# barebonesarduino.net
KiCad netlist of a schematic drawn in EAGLE
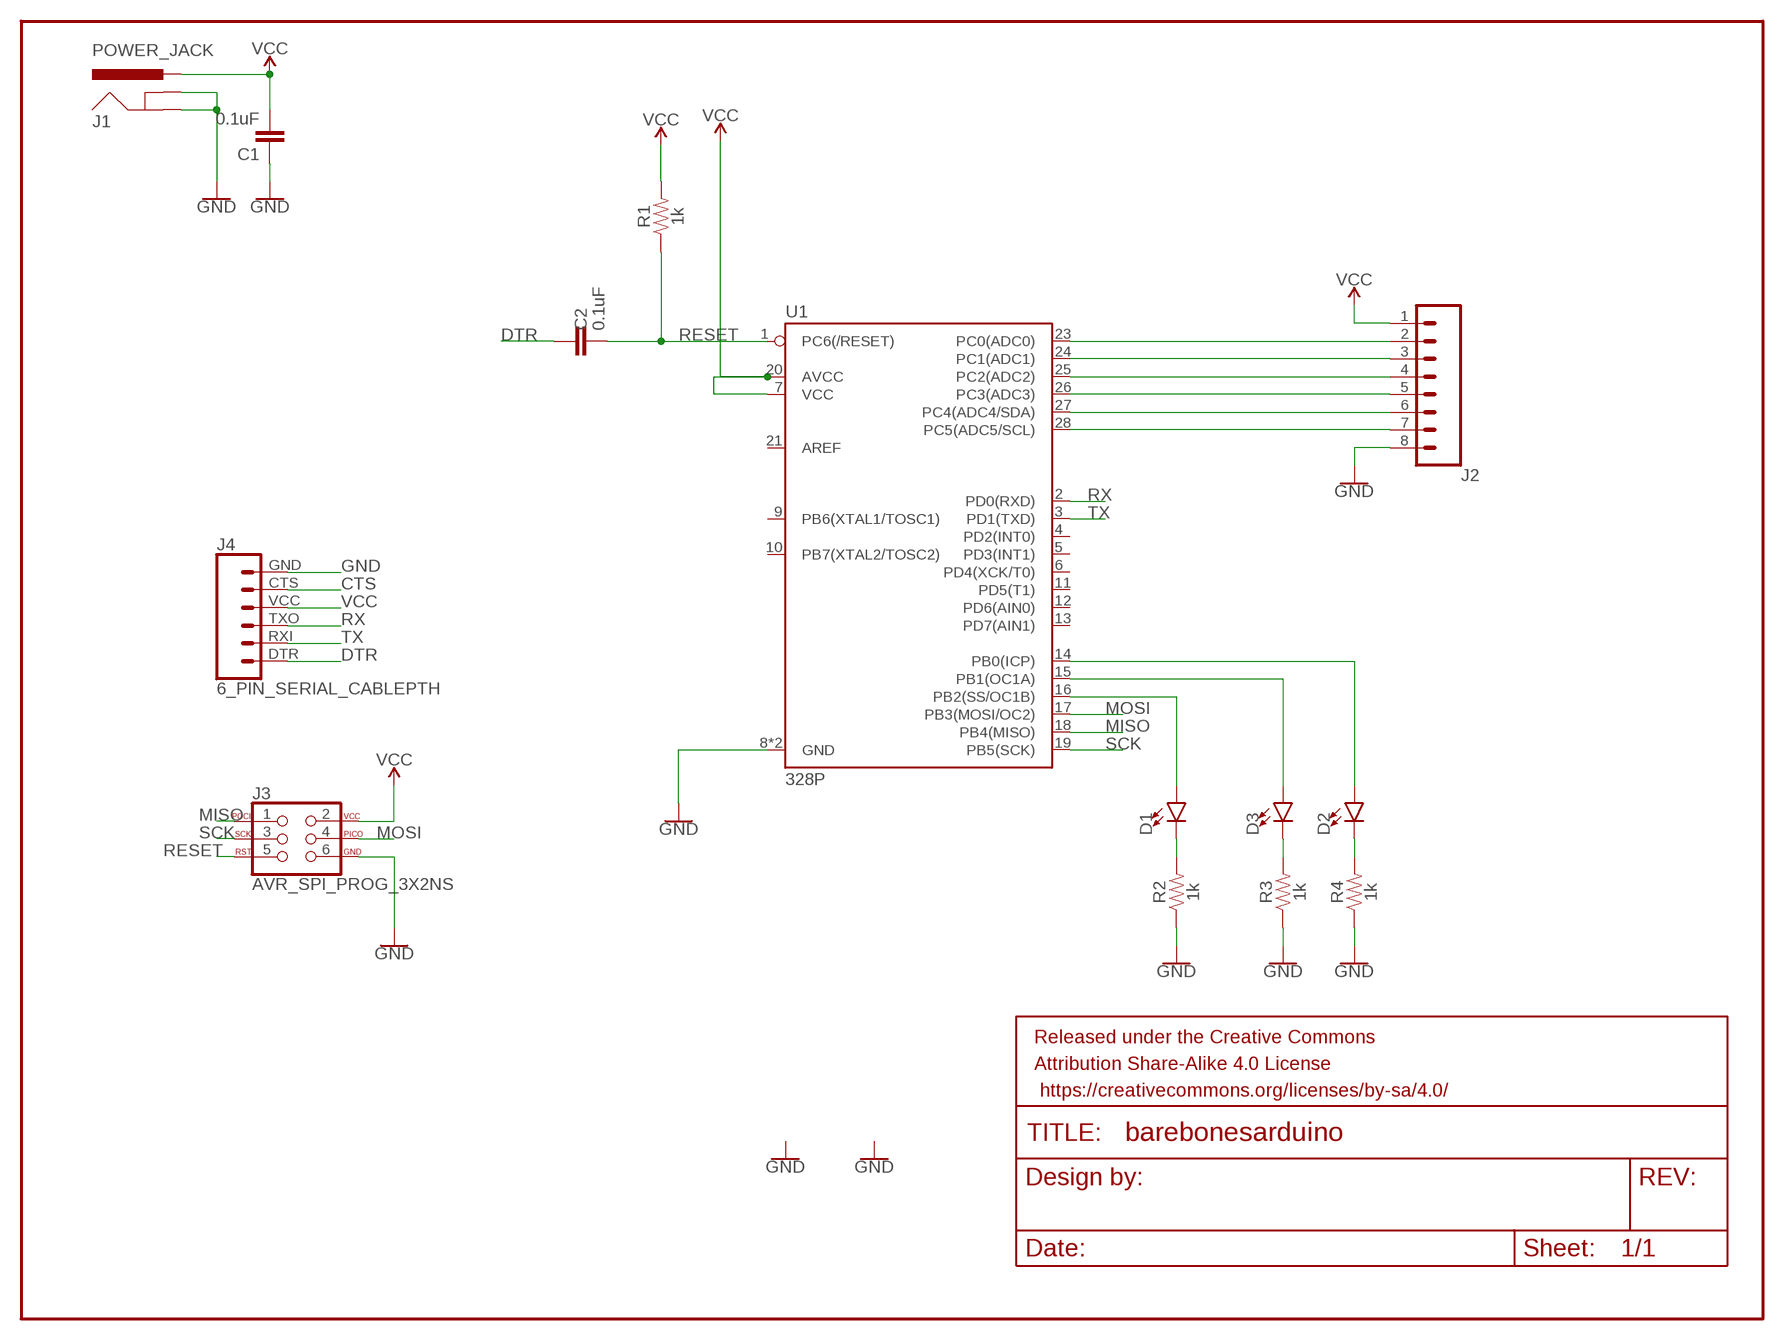
[diagram p0: schematic, sheet 1]

(export (version "E")
  (design (tool "Eeschema 10.0.6"))
  (components
    (comp (ref "C1")
      (value "0.1uF")
      (footprint "eagle-import:CAP-PTH-SMALL-KIT")
      (libsource (lib "eagle-import") (part "0.1UF-KIT-EZ-50V-20%"))
    )
    (comp (ref "C2")
      (value "0.1uF")
      (footprint "eagle-import:CAP-PTH-SMALL-KIT")
      (libsource (lib "eagle-import") (part "0.1UF-KIT-EZ-50V-20%"))
    )
    (comp (ref "D1")
      (value "LED5MM")
      (footprint "eagle-import:LED_5MM")
      (libsource (lib "eagle-import") (part "LED5MM"))
    )
    (comp (ref "D2")
      (value "LED5MM")
      (footprint "eagle-import:LED_5MM")
      (libsource (lib "eagle-import") (part "LED5MM"))
    )
    (comp (ref "D3")
      (value "LED5MM")
      (footprint "eagle-import:LED_5MM")
      (libsource (lib "eagle-import") (part "LED5MM"))
    )
    (comp (ref "FRAME1")
      (value "FRAME-LETTER")
      (footprint "eagle-import:CREATIVE_COMMONS")
      (libsource (lib "eagle-import") (part "FRAME-LETTER"))
    )
    (comp (ref "J1")
      (value "POWER_JACK")
      (footprint "eagle-import:POWER_JACK_PTH")
      (libsource (lib "eagle-import") (part "POWER_JACK"))
    )
    (comp (ref "J2")
      (value "CONN_08\"")
      (footprint "eagle-import:1X08")
      (libsource (lib "eagle-import") (part "CONN_08{dblquote}"))
    )
    (comp (ref "J3")
      (value "AVR_SPI_PROG_3X2NS")
      (footprint "eagle-import:2X3-NS")
      (libsource (lib "eagle-import") (part "AVR_SPI_PROG_3X2NS"))
    )
    (comp (ref "J4")
      (value "6_PIN_SERIAL_CABLEPTH")
      (footprint "eagle-import:FTDI_BASIC")
      (libsource (lib "eagle-import") (part "6_PIN_SERIAL_CABLEPTH"))
    )
    (comp (ref "R1")
      (value "1k")
      (footprint "eagle-import:AXIAL-0.1-KIT")
      (libsource (lib "eagle-import") (part "1KOHM-VERT_KIT-1/4W-1%"))
    )
    (comp (ref "R2")
      (value "1k")
      (footprint "eagle-import:AXIAL-0.1-KIT")
      (libsource (lib "eagle-import") (part "1KOHM-VERT_KIT-1/4W-1%"))
    )
    (comp (ref "R3")
      (value "1k")
      (footprint "eagle-import:AXIAL-0.1-KIT")
      (libsource (lib "eagle-import") (part "1KOHM-VERT_KIT-1/4W-1%"))
    )
    (comp (ref "R4")
      (value "1k")
      (footprint "eagle-import:AXIAL-0.1-KIT")
      (libsource (lib "eagle-import") (part "1KOHM-VERT_KIT-1/4W-1%"))
    )
    (comp (ref "U1")
      (value "328P")
      (footprint "eagle-import:DIP28")
      (libsource (lib "eagle-import") (part "ATMEGA328P_PDIP"))
    )
  )
  (nets
    (net (code "1") (name "/CTS") (class "Default")
      (node (ref "J4") (pin "CTS") (pinfunction "5_CTS") (pintype "passive"))
    )
    (net (code "2") (name "/DTR") (class "Default")
      (node (ref "C2") (pin "1") (pinfunction "1_1") (pintype "passive"))
      (node (ref "J4") (pin "DTR") (pinfunction "1_DTR") (pintype "passive"))
    )
    (net (code "3") (name "/MISO") (class "Default")
      (node (ref "J3") (pin "1") (pinfunction "1_1") (pintype "passive"))
      (node (ref "U1") (pin "18") (pinfunction "PB4(MISO)_18") (pintype "bidirectional"))
    )
    (net (code "4") (name "/MOSI") (class "Default")
      (node (ref "J3") (pin "4") (pinfunction "4_4") (pintype "passive"))
      (node (ref "U1") (pin "17") (pinfunction "PB3(MOSI/OC2)_17") (pintype "bidirectional"))
    )
    (net (code "5") (name "/RESET") (class "Default")
      (node (ref "C2") (pin "2") (pinfunction "2_2") (pintype "passive"))
      (node (ref "J3") (pin "5") (pinfunction "5_5") (pintype "passive"))
      (node (ref "R1") (pin "P$1") (pinfunction "1_P$1") (pintype "passive"))
      (node (ref "U1") (pin "1") (pinfunction "PC6(/RESET)_1") (pintype "bidirectional"))
    )
    (net (code "6") (name "/RX") (class "Default")
      (node (ref "J4") (pin "TXO") (pinfunction "3_TXO") (pintype "passive"))
      (node (ref "U1") (pin "2") (pinfunction "PD0(RXD)_2") (pintype "bidirectional"))
    )
    (net (code "7") (name "/SCK") (class "Default")
      (node (ref "J3") (pin "3") (pinfunction "3_3") (pintype "passive"))
      (node (ref "U1") (pin "19") (pinfunction "PB5(SCK)_19") (pintype "bidirectional"))
    )
    (net (code "8") (name "/TX") (class "Default")
      (node (ref "J4") (pin "RXI") (pinfunction "2_RXI") (pintype "passive"))
      (node (ref "U1") (pin "3") (pinfunction "PD1(TXD)_3") (pintype "bidirectional"))
    )
    (net (code "9") (name "GND") (class "Default")
      (node (ref "C1") (pin "1") (pinfunction "1_1") (pintype "passive"))
      (node (ref "J1") (pin "GND") (pinfunction "GND_GND") (pintype "bidirectional"))
      (node (ref "J1") (pin "GNDBREAK") (pinfunction "GNDBREAK_GNDBREAK") (pintype "bidirectional"))
      (node (ref "J2") (pin "8") (pinfunction "8_8") (pintype "passive"))
      (node (ref "J3") (pin "6") (pinfunction "6_6") (pintype "passive"))
      (node (ref "J4") (pin "GND") (pinfunction "6_GND") (pintype "passive"))
      (node (ref "R2") (pin "P$1") (pinfunction "1_P$1") (pintype "passive"))
      (node (ref "R3") (pin "P$1") (pinfunction "1_P$1") (pintype "passive"))
      (node (ref "R4") (pin "P$1") (pinfunction "1_P$1") (pintype "passive"))
      (node (ref "U1") (pin "22") (pinfunction "GND_22") (pintype "bidirectional"))
      (node (ref "U1") (pin "8") (pinfunction "GND_8") (pintype "bidirectional"))
    )
    (net (code "10") (name "Net-(D1-C)") (class "Default")
      (node (ref "D1") (pin "K") (pinfunction "C_K") (pintype "passive"))
      (node (ref "R2") (pin "P$2") (pinfunction "2_P$2") (pintype "passive"))
    )
    (net (code "11") (name "Net-(D2-C)") (class "Default")
      (node (ref "D2") (pin "K") (pinfunction "C_K") (pintype "passive"))
      (node (ref "R4") (pin "P$2") (pinfunction "2_P$2") (pintype "passive"))
    )
    (net (code "12") (name "Net-(D3-C)") (class "Default")
      (node (ref "D3") (pin "K") (pinfunction "C_K") (pintype "passive"))
      (node (ref "R3") (pin "P$2") (pinfunction "2_P$2") (pintype "passive"))
    )
    (net (code "13") (name "Net-(U1-PB0(ICP))") (class "Default")
      (node (ref "D2") (pin "A") (pinfunction "A_A") (pintype "passive"))
      (node (ref "U1") (pin "14") (pinfunction "PB0(ICP)_14") (pintype "bidirectional"))
    )
    (net (code "14") (name "Net-(U1-PB1(OC1A))") (class "Default")
      (node (ref "D3") (pin "A") (pinfunction "A_A") (pintype "passive"))
      (node (ref "U1") (pin "15") (pinfunction "PB1(OC1A)_15") (pintype "bidirectional"))
    )
    (net (code "15") (name "Net-(U1-PB2(SS{slash}OC1B))") (class "Default")
      (node (ref "D1") (pin "A") (pinfunction "A_A") (pintype "passive"))
      (node (ref "U1") (pin "16") (pinfunction "PB2(SS/OC1B)_16") (pintype "bidirectional"))
    )
    (net (code "16") (name "Net-(U1-PC0(ADC0))") (class "Default")
      (node (ref "J2") (pin "2") (pinfunction "2_2") (pintype "passive"))
      (node (ref "U1") (pin "23") (pinfunction "PC0(ADC0)_23") (pintype "bidirectional"))
    )
    (net (code "17") (name "Net-(U1-PC1(ADC1))") (class "Default")
      (node (ref "J2") (pin "3") (pinfunction "3_3") (pintype "passive"))
      (node (ref "U1") (pin "24") (pinfunction "PC1(ADC1)_24") (pintype "bidirectional"))
    )
    (net (code "18") (name "Net-(U1-PC2(ADC2))") (class "Default")
      (node (ref "J2") (pin "4") (pinfunction "4_4") (pintype "passive"))
      (node (ref "U1") (pin "25") (pinfunction "PC2(ADC2)_25") (pintype "bidirectional"))
    )
    (net (code "19") (name "Net-(U1-PC3(ADC3))") (class "Default")
      (node (ref "J2") (pin "5") (pinfunction "5_5") (pintype "passive"))
      (node (ref "U1") (pin "26") (pinfunction "PC3(ADC3)_26") (pintype "bidirectional"))
    )
    (net (code "20") (name "Net-(U1-PC4(ADC4{slash}SDA))") (class "Default")
      (node (ref "J2") (pin "6") (pinfunction "6_6") (pintype "passive"))
      (node (ref "U1") (pin "27") (pinfunction "PC4(ADC4/SDA)_27") (pintype "bidirectional"))
    )
    (net (code "21") (name "Net-(U1-PC5(ADC5{slash}SCL))") (class "Default")
      (node (ref "J2") (pin "7") (pinfunction "7_7") (pintype "passive"))
      (node (ref "U1") (pin "28") (pinfunction "PC5(ADC5/SCL)_28") (pintype "bidirectional"))
    )
    (net (code "22") (name "VCC") (class "Default")
      (node (ref "C1") (pin "2") (pinfunction "2_2") (pintype "passive"))
      (node (ref "J1") (pin "PWR") (pinfunction "PWR_PWR") (pintype "bidirectional"))
      (node (ref "J2") (pin "1") (pinfunction "1_1") (pintype "passive"))
      (node (ref "J3") (pin "2") (pinfunction "2_2") (pintype "passive"))
      (node (ref "J4") (pin "VCC") (pinfunction "4_VCC") (pintype "passive"))
      (node (ref "R1") (pin "P$2") (pinfunction "2_P$2") (pintype "passive"))
      (node (ref "U1") (pin "20") (pinfunction "AVCC_20") (pintype "bidirectional"))
      (node (ref "U1") (pin "7") (pinfunction "VCC_7") (pintype "bidirectional"))
    )
    (net (code "23") (name "unconnected-(U1-AREF-Pad21)") (class "Default")
      (node (ref "U1") (pin "21") (pinfunction "AREF_21") (pintype "bidirectional"))
    )
    (net (code "24") (name "unconnected-(U1-PB6(XTAL1{slash}TOSC1)-Pad9)") (class "Default")
      (node (ref "U1") (pin "9") (pinfunction "PB6(XTAL1/TOSC1)_9") (pintype "bidirectional"))
    )
    (net (code "25") (name "unconnected-(U1-PB7(XTAL2{slash}TOSC2)-Pad10)") (class "Default")
      (node (ref "U1") (pin "10") (pinfunction "PB7(XTAL2/TOSC2)_10") (pintype "bidirectional"))
    )
    (net (code "26") (name "unconnected-(U1-PD2(INT0)-Pad4)") (class "Default")
      (node (ref "U1") (pin "4") (pinfunction "PD2(INT0)_4") (pintype "bidirectional"))
    )
    (net (code "27") (name "unconnected-(U1-PD3(INT1)-Pad5)") (class "Default")
      (node (ref "U1") (pin "5") (pinfunction "PD3(INT1)_5") (pintype "bidirectional"))
    )
    (net (code "28") (name "unconnected-(U1-PD4(XCK{slash}T0)-Pad6)") (class "Default")
      (node (ref "U1") (pin "6") (pinfunction "PD4(XCK/T0)_6") (pintype "bidirectional"))
    )
    (net (code "29") (name "unconnected-(U1-PD5(T1)-Pad11)") (class "Default")
      (node (ref "U1") (pin "11") (pinfunction "PD5(T1)_11") (pintype "bidirectional"))
    )
    (net (code "30") (name "unconnected-(U1-PD6(AIN0)-Pad12)") (class "Default")
      (node (ref "U1") (pin "12") (pinfunction "PD6(AIN0)_12") (pintype "bidirectional"))
    )
    (net (code "31") (name "unconnected-(U1-PD7(AIN1)-Pad13)") (class "Default")
      (node (ref "U1") (pin "13") (pinfunction "PD7(AIN1)_13") (pintype "bidirectional"))
    )
  )
)
